# SM2_GPS_Module.net
KiCad netlist of a schematic drawn in Altium Designer
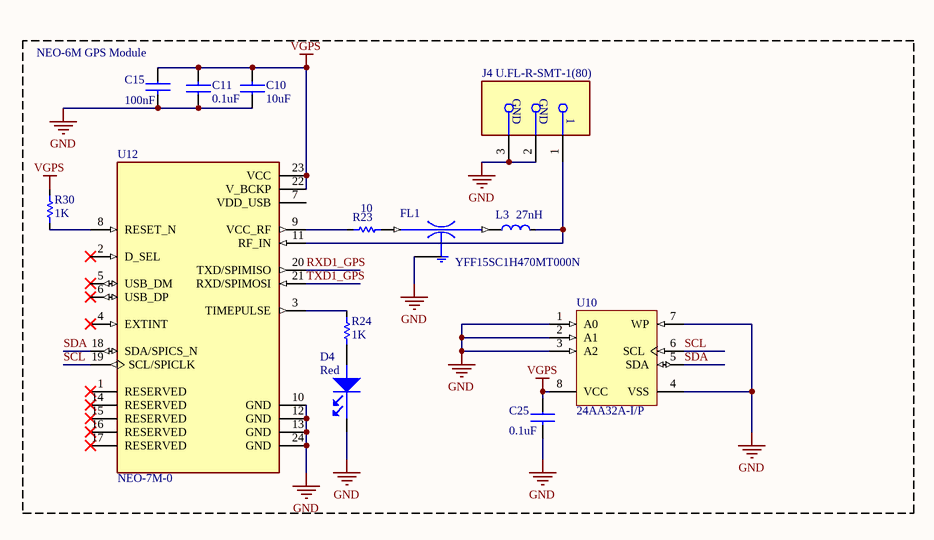
[diagram p0: SM2_GPS_Module.SchDoc]

(export (version "E")
  (design (tool "Eeschema 10.0.6"))
  (components
    (comp (ref "C10")
      (value "10uF")
      (footprint "CAPC1005X56N")
      (description "CAP CER 0.1uF 16V 0402")
      (fields (field (name "PARTNUMBER") "TCC0402X5R104M160AT") (field (name "MANUFACTURER") "CCTC"))
      (libsource (lib "MAR") (part "CAP_0402"))
    )
    (comp (ref "C11")
      (value "0.1uF")
      (footprint "CAPC1005X56N")
      (description "CAP CER 0.1uF 16V 0402")
      (fields (field (name "PARTNUMBER") "TCC0402X5R104M160AT") (field (name "MANUFACTURER") "CCTC"))
      (libsource (lib "MAR") (part "CAP_0402"))
    )
    (comp (ref "C15")
      (value "100nF")
      (footprint "CAPC1005X56N")
      (description "CAP CER 0.1uF 16V 0402")
      (fields (field (name "PARTNUMBER") "TCC0402X5R104M160AT") (field (name "MANUFACTURER") "CCTC"))
      (libsource (lib "MAR") (part "CAP_0402"))
    )
    (comp (ref "C25")
      (value "0.1uF")
      (footprint "CAPC1005X56N")
      (description "CAP CER 0.1uF 16V 0402")
      (fields (field (name "PARTNUMBER") "TCC0402X5R104M160AT") (field (name "MANUFACTURER") "CCTC"))
      (libsource (lib "MAR") (part "CAP_0402"))
    )
    (comp (ref "D4")
      (value "Red")
      (footprint "LED1608X55N-RED")
      (description "LED RED CLEAR 0603 SMD")
      (fields (field (name "MANUFACTURER") "FNO") (field (name "PARTNUMBER") "FC-DA1608HRK-620D"))
      (libsource (lib "MAR") (part "LED_0603"))
    )
    (comp (ref "FL1")
      (value "YFF15SC1H470MT000N")
      (footprint "FIL_YFF15SC1H470MT000N")
      (libsource (lib "YFF15SC1H470MT000N") (part "YFF15SC1H470MT000N"))
    )
    (comp (ref "J4")
      (value "U.FL-R-SMT-1(80)")
      (footprint "FP-U_FL-R-SMT-1_80-MFG")
      (description "CONN U.FL RCPT STR 50 OHM SMD")
      (libsource (lib "Altium Content Vault") (part "ad010367dc7cd7c7a13299a56582dd6"))
    )
    (comp (ref "L3")
      (value "27nH")
      (footprint "RESC1005X40L")
      (description "Inductor 1.8nH 0402")
      (fields (field (name "PARTNUMBER") "BKW0603UC1N8KGT") (field (name "MANUFACTURER") "GFBE"))
      (libsource (lib "MAR") (part "Inductor"))
    )
    (comp (ref "R23")
      (value "10")
      (footprint "RESC1005X40L")
      (description "RES SMD 100K OHM 0402")
      (fields (field (name "MANUFACTURER") "Uniroyal Elec") (field (name "PARTNUMBER") "0402WGF1003TCE"))
      (libsource (lib "MAR") (part "RES_0603"))
    )
    (comp (ref "R24")
      (value "1K")
      (footprint "RESC1005X40L")
      (description "RES SMD 100K OHM 0402")
      (fields (field (name "MANUFACTURER") "Uniroyal Elec") (field (name "PARTNUMBER") "0402WGF1003TCE"))
      (libsource (lib "MAR") (part "RES_0603"))
    )
    (comp (ref "R30")
      (value "1K")
      (footprint "RESC1005X40L")
      (description "RES SMD 100K OHM 0402")
      (fields (field (name "MANUFACTURER") "Uniroyal Elec") (field (name "PARTNUMBER") "0402WGF1003TCE"))
      (libsource (lib "MAR") (part "RES_0603"))
    )
    (comp (ref "U10")
      (value "24AA32A-I/P")
      (footprint "PDIP300-P8")
      (description "32Kbit, 400kHz, 1.7V, I2C Serial EEPROM, 8-Pin PDIP, Industrial Temperature")
      (libsource (lib "Altium Content Vault") (part "MEM-SEEPROM-34AA02-IL8"))
    )
    (comp (ref "U12")
      (value "NEO-7M-0")
      (footprint "XCVR_NEO-7M-0")
      (description "series RF Receiver GLONASS, GNSS, GPS 1.575GHz -161dBm - - -")
      (fields (field (name "MF") "U-Blox America"))
      (libsource (lib "NEO-7M-0") (part "NEO-7M-0"))
    )
  )
  (nets
    (net (code "1") (name "/RXD1_GPS") (class "Default")
      (node (ref "U12") (pin "20") (pinfunction "TXD/SPIMISO_20") (pintype "output"))
    )
    (net (code "2") (name "/SCL") (class "Default")
      (node (ref "U10") (pin "6") (pinfunction "SCL_6") (pintype "input"))
      (node (ref "U12") (pin "19") (pinfunction "SCL/SPICLK_19") (pintype "output"))
    )
    (net (code "3") (name "/SDA") (class "Default")
      (node (ref "U10") (pin "5") (pinfunction "SDA_5") (pintype "bidirectional"))
      (node (ref "U12") (pin "18") (pinfunction "SDA/SPICS_N_18") (pintype "bidirectional"))
    )
    (net (code "4") (name "/TXD1_GPS") (class "Default")
      (node (ref "U12") (pin "21") (pinfunction "RXD/SPIMOSI_21") (pintype "input"))
    )
    (net (code "5") (name "GND") (class "Default")
      (node (ref "C10") (pin "1") (pinfunction "1_1") (pintype "passive"))
      (node (ref "C11") (pin "1") (pinfunction "1_1") (pintype "passive"))
      (node (ref "C15") (pin "2") (pinfunction "2_2") (pintype "passive"))
      (node (ref "C25") (pin "2") (pinfunction "2_2") (pintype "passive"))
      (node (ref "D4") (pin "1") (pinfunction "CATHODE_1") (pintype "passive"))
      (node (ref "FL1") (pin "3") (pinfunction "GND_3") (pintype "power_in"))
      (node (ref "J4") (pin "2") (pinfunction "GND_2") (pintype "power_in"))
      (node (ref "J4") (pin "3") (pinfunction "GND_3") (pintype "power_in"))
      (node (ref "U10") (pin "1") (pinfunction "A0_1") (pintype "input"))
      (node (ref "U10") (pin "2") (pinfunction "A1_2") (pintype "input"))
      (node (ref "U10") (pin "3") (pinfunction "A2_3") (pintype "input"))
      (node (ref "U10") (pin "4") (pinfunction "VSS_4") (pintype "power_in"))
      (node (ref "U10") (pin "7") (pinfunction "WP_7") (pintype "input"))
      (node (ref "U12") (pin "10") (pinfunction "GND_10") (pintype "power_in"))
      (node (ref "U12") (pin "12") (pinfunction "GND_12") (pintype "power_in"))
      (node (ref "U12") (pin "13") (pinfunction "GND_13") (pintype "power_in"))
      (node (ref "U12") (pin "24") (pinfunction "GND_24") (pintype "power_in"))
    )
    (net (code "6") (name "Net-(D4-ANODE)") (class "Default")
      (node (ref "D4") (pin "2") (pinfunction "ANODE_2") (pintype "passive"))
      (node (ref "R24") (pin "2") (pintype "passive"))
    )
    (net (code "7") (name "Net-(FL1-IN)") (class "Default")
      (node (ref "FL1") (pin "1") (pinfunction "IN_1") (pintype "input"))
      (node (ref "R23") (pin "2") (pintype "passive"))
    )
    (net (code "8") (name "Net-(FL1-OUT)") (class "Default")
      (node (ref "FL1") (pin "2") (pinfunction "OUT_2") (pintype "output"))
      (node (ref "L3") (pin "1") (pinfunction "1_1") (pintype "passive"))
    )
    (net (code "9") (name "Net-(U12-RESET_N)") (class "Default")
      (node (ref "R30") (pin "2") (pintype "passive"))
      (node (ref "U12") (pin "8") (pinfunction "RESET_N_8") (pintype "input"))
    )
    (net (code "10") (name "Net-(U12-RF_IN)") (class "Default")
      (node (ref "J4") (pin "1") (pinfunction "1_1") (pintype "passive"))
      (node (ref "L3") (pin "2") (pinfunction "2_2") (pintype "passive"))
      (node (ref "U12") (pin "11") (pinfunction "RF_IN_11") (pintype "input"))
    )
    (net (code "11") (name "Net-(U12-TIMEPULSE)") (class "Default")
      (node (ref "R24") (pin "1") (pintype "passive"))
      (node (ref "U12") (pin "3") (pinfunction "TIMEPULSE_3") (pintype "output"))
    )
    (net (code "12") (name "Net-(U12-VCC_RF)") (class "Default")
      (node (ref "R23") (pin "1") (pintype "passive"))
      (node (ref "U12") (pin "9") (pinfunction "VCC_RF_9") (pintype "output"))
    )
    (net (code "13") (name "VGPS") (class "Default")
      (node (ref "C10") (pin "2") (pinfunction "2_2") (pintype "passive"))
      (node (ref "C11") (pin "2") (pinfunction "2_2") (pintype "passive"))
      (node (ref "C15") (pin "1") (pinfunction "1_1") (pintype "passive"))
      (node (ref "C25") (pin "1") (pinfunction "1_1") (pintype "passive"))
      (node (ref "R30") (pin "1") (pintype "passive"))
      (node (ref "U10") (pin "8") (pinfunction "VCC_8") (pintype "power_in"))
      (node (ref "U12") (pin "22") (pinfunction "V_BCKP_22") (pintype "power_in"))
      (node (ref "U12") (pin "23") (pinfunction "VCC_23") (pintype "power_in"))
    )
    (net (code "14") (name "unconnected-(U12-D_SEL-Pad2)") (class "Default")
      (node (ref "U12") (pin "2") (pinfunction "D_SEL_2") (pintype "input+no_connect"))
    )
    (net (code "15") (name "unconnected-(U12-EXTINT-Pad4)") (class "Default")
      (node (ref "U12") (pin "4") (pinfunction "EXTINT_4") (pintype "input+no_connect"))
    )
    (net (code "16") (name "unconnected-(U12-RESERVED-Pad1)") (class "Default")
      (node (ref "U12") (pin "1") (pinfunction "RESERVED_1") (pintype "passive+no_connect"))
    )
    (net (code "17") (name "unconnected-(U12-RESERVED-Pad14)") (class "Default")
      (node (ref "U12") (pin "14") (pinfunction "RESERVED_14") (pintype "passive+no_connect"))
    )
    (net (code "18") (name "unconnected-(U12-RESERVED-Pad15)") (class "Default")
      (node (ref "U12") (pin "15") (pinfunction "RESERVED_15") (pintype "passive+no_connect"))
    )
    (net (code "19") (name "unconnected-(U12-RESERVED-Pad16)") (class "Default")
      (node (ref "U12") (pin "16") (pinfunction "RESERVED_16") (pintype "passive+no_connect"))
    )
    (net (code "20") (name "unconnected-(U12-RESERVED-Pad17)") (class "Default")
      (node (ref "U12") (pin "17") (pinfunction "RESERVED_17") (pintype "passive+no_connect"))
    )
    (net (code "21") (name "unconnected-(U12-USB_DM-Pad5)") (class "Default")
      (node (ref "U12") (pin "5") (pinfunction "USB_DM_5") (pintype "bidirectional+no_connect"))
    )
    (net (code "22") (name "unconnected-(U12-USB_DP-Pad6)") (class "Default")
      (node (ref "U12") (pin "6") (pinfunction "USB_DP_6") (pintype "bidirectional+no_connect"))
    )
    (net (code "23") (name "unconnected-(U12-VDD_USB-Pad7)") (class "Default")
      (node (ref "U12") (pin "7") (pinfunction "VDD_USB_7") (pintype "power_in"))
    )
  )
)
